# Seeeduino_v4_0.net
KiCad netlist of a schematic drawn in EAGLE
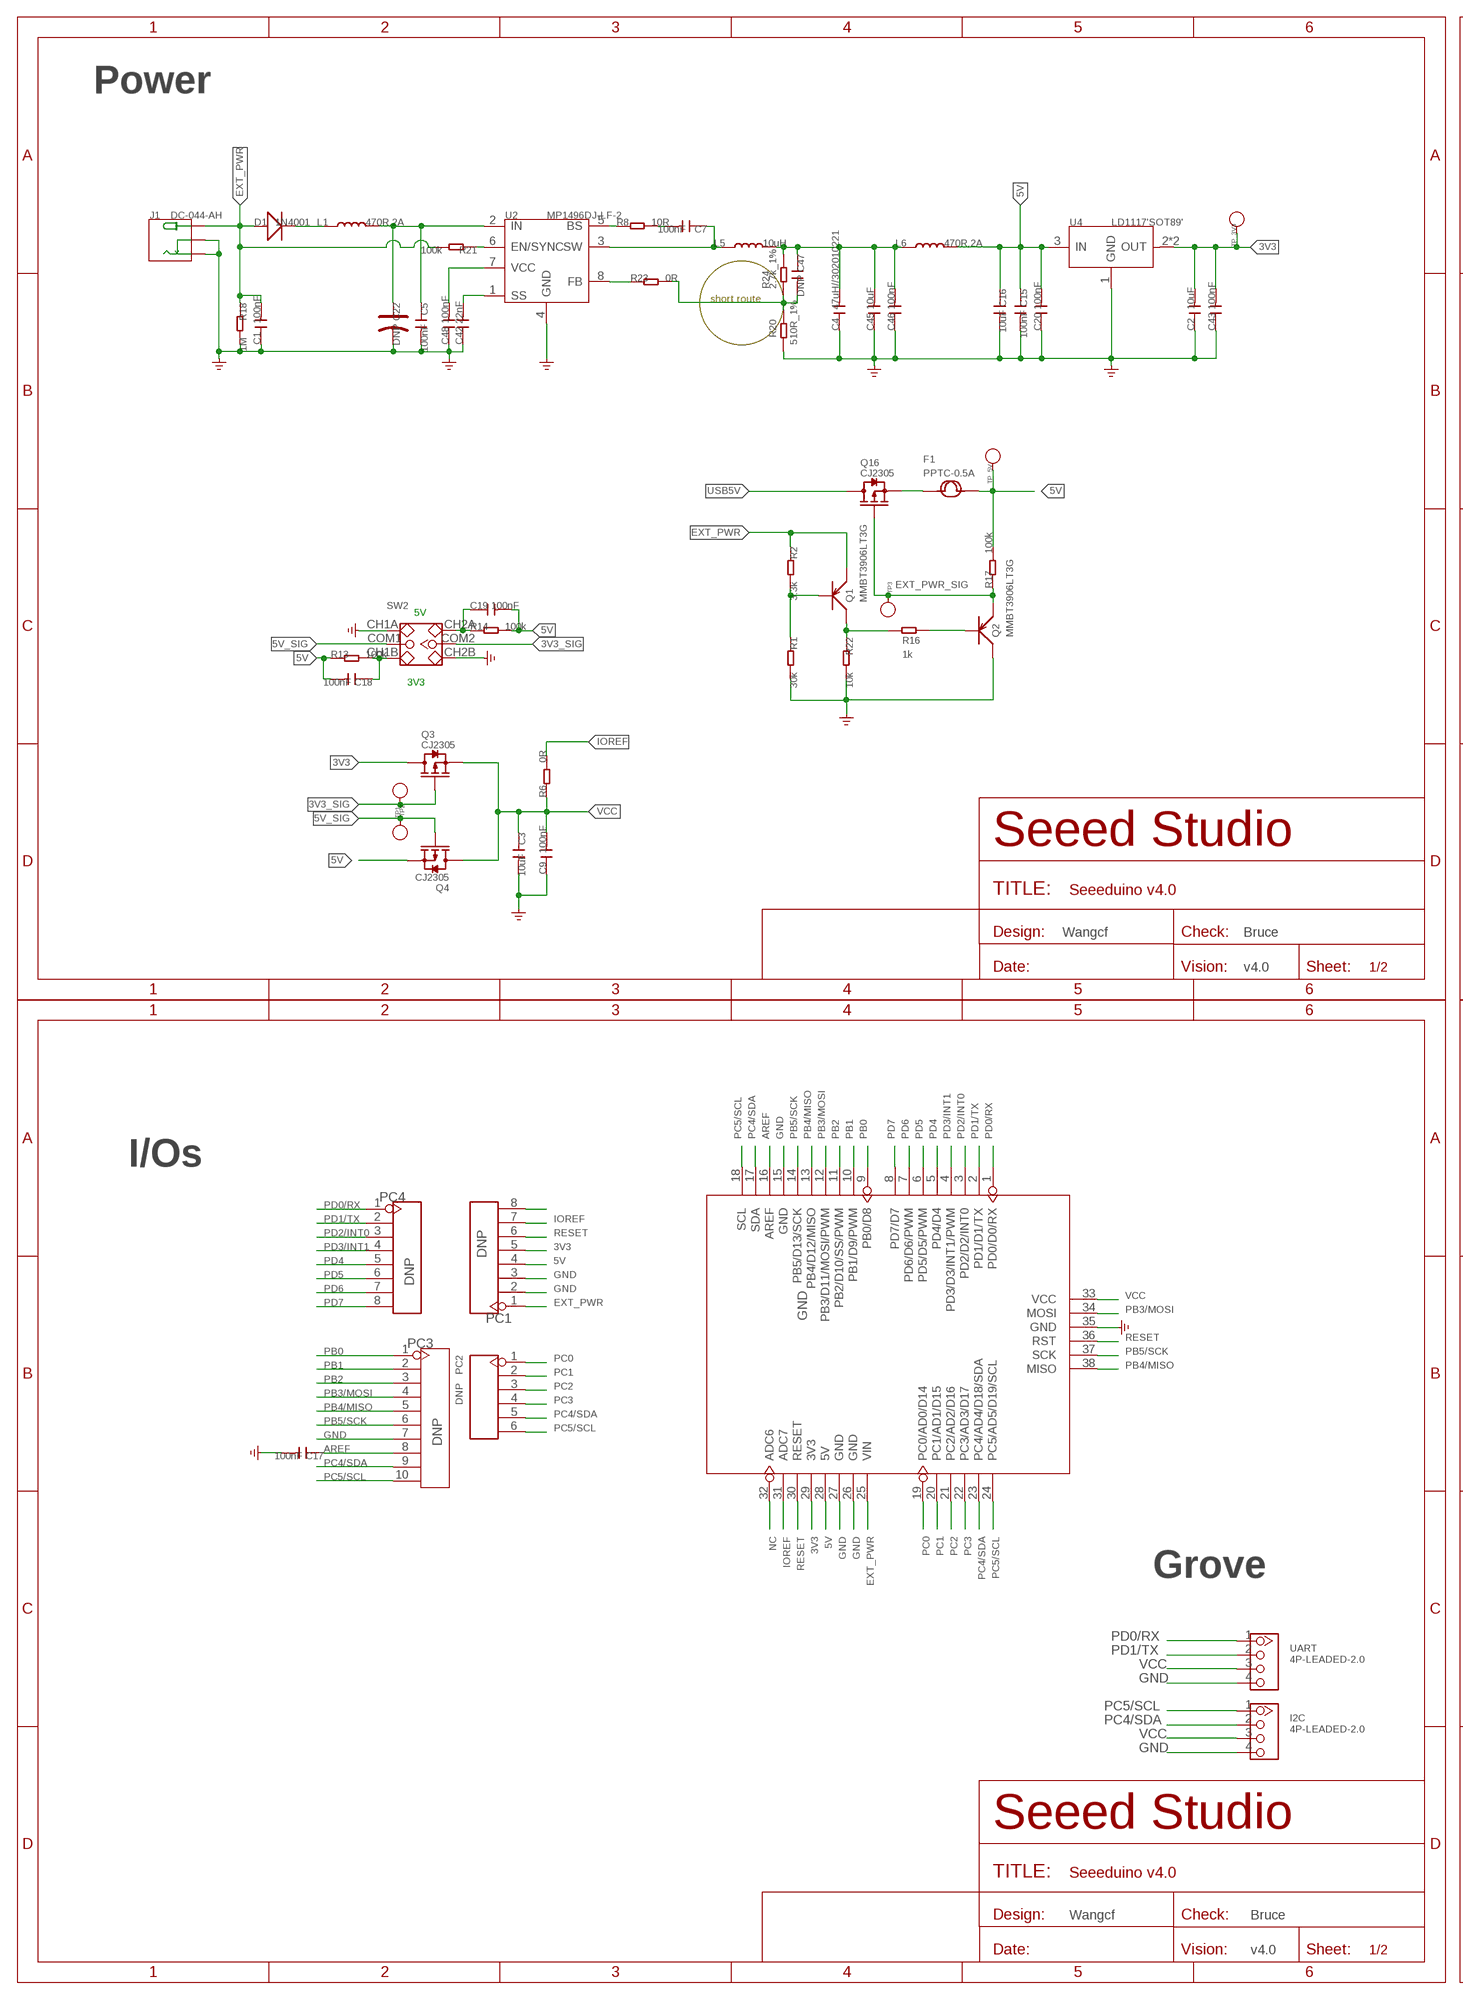
[diagram p0: schematic, sheet 1, part 1 of 2]
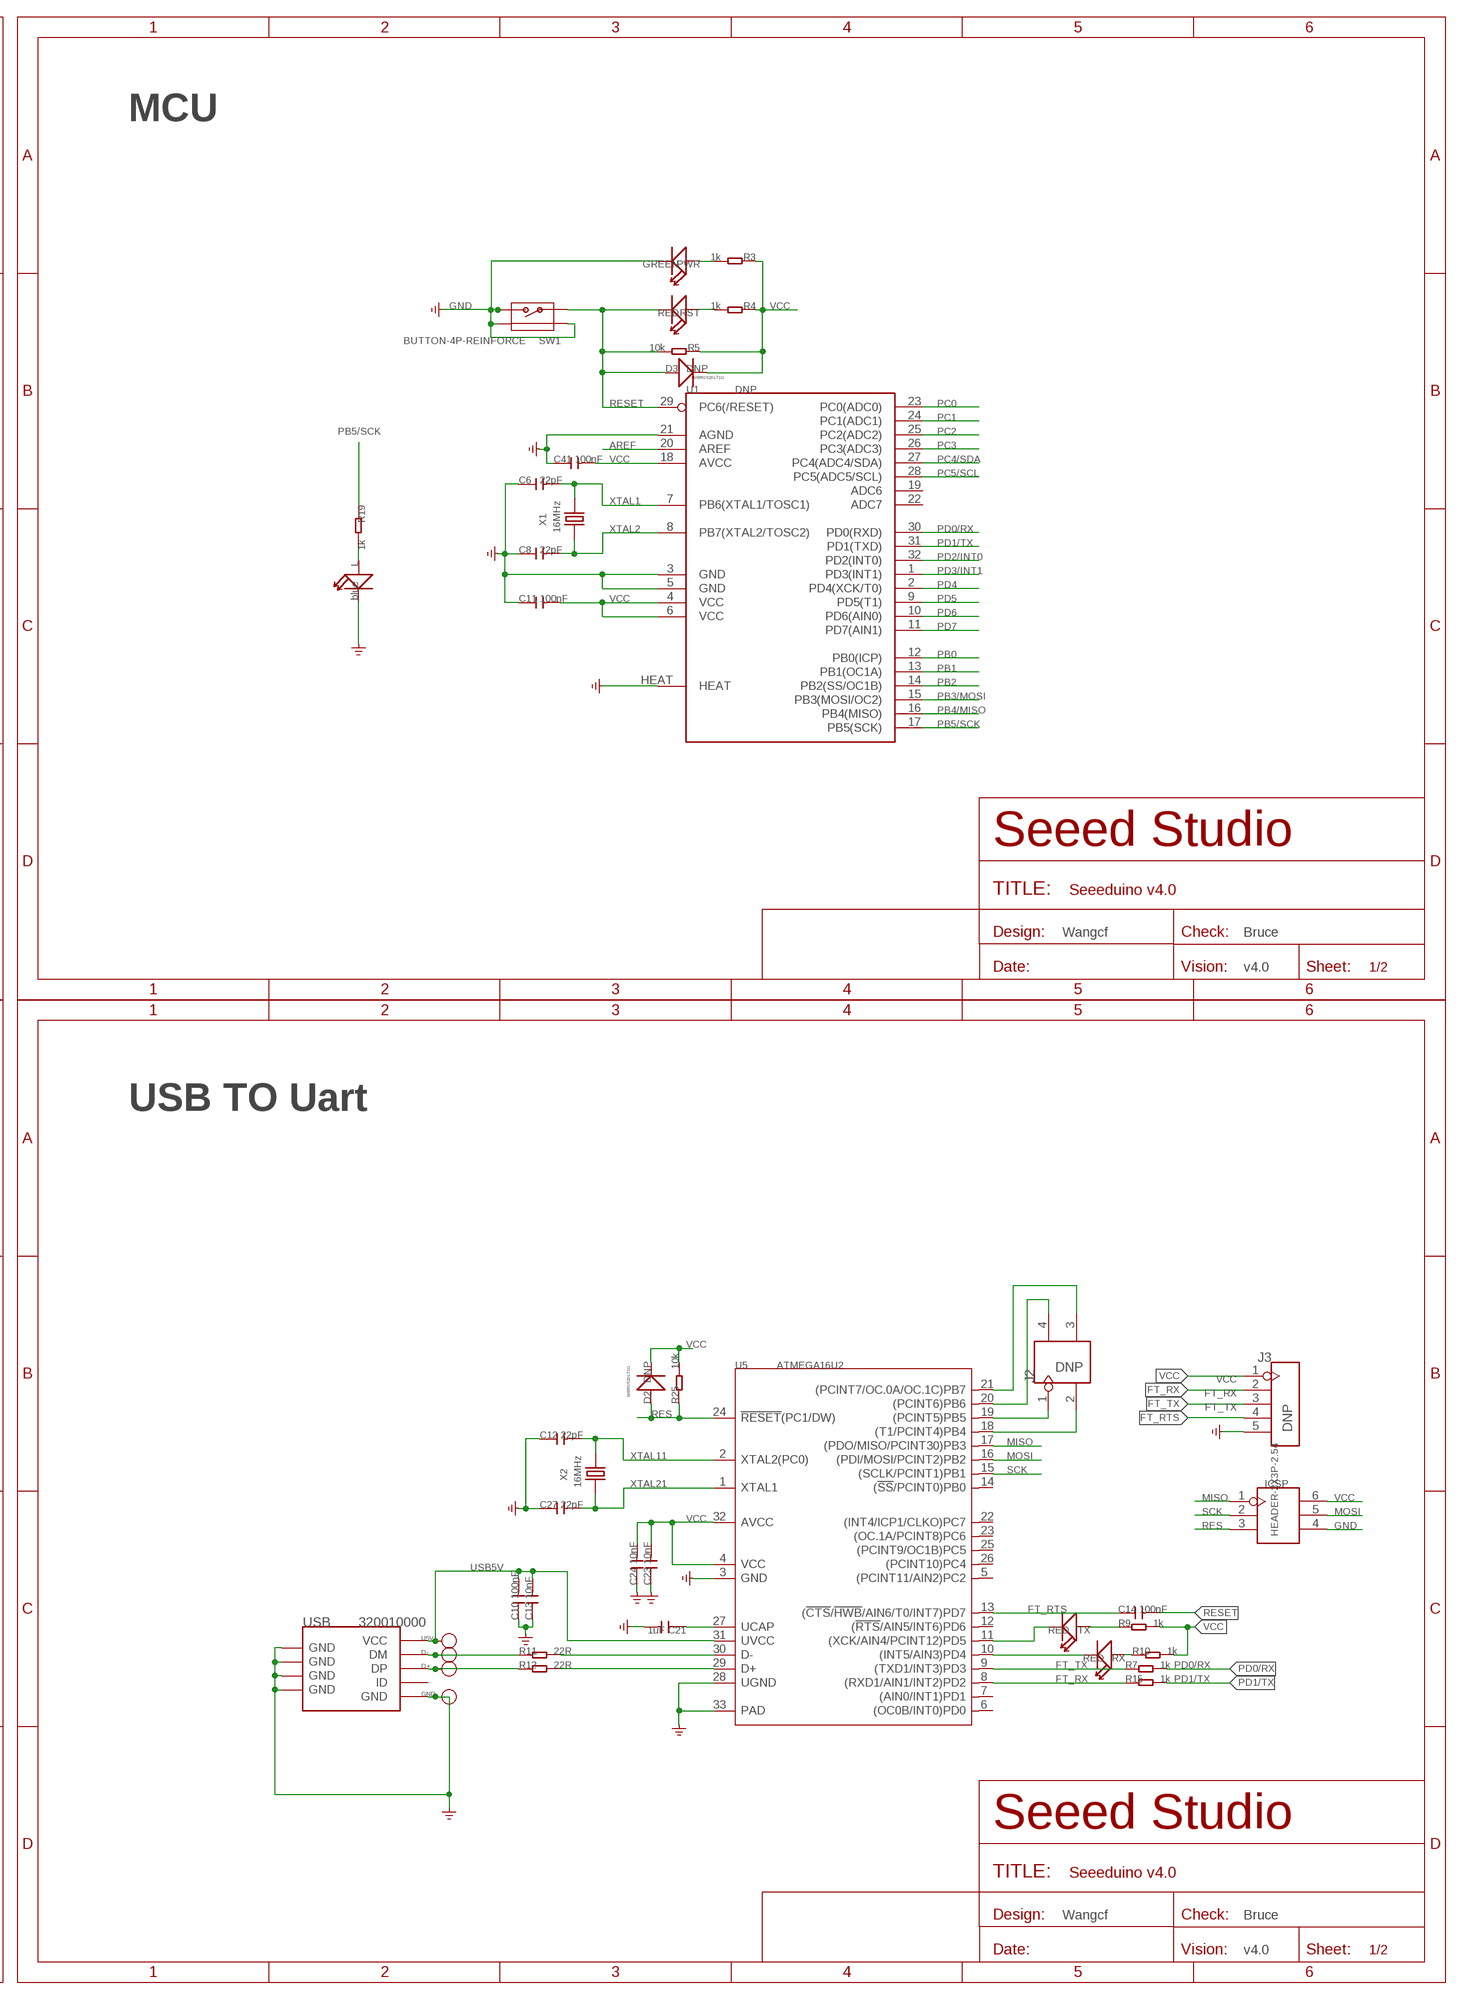
[diagram p1: schematic, sheet 1, part 2 of 2]
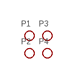
[diagram p2: schematic, sheet 2]

(export (version "E")
  (design (tool "Eeschema 10.0.6"))
  (components
    (comp (ref "C1")
      (value "100nF")
      (footprint "eagle-import:C0603")
      (libsource (lib "eagle-import") (part "C-0603"))
    )
    (comp (ref "C2")
      (value "10uF")
      (footprint "eagle-import:C0805")
      (libsource (lib "eagle-import") (part "C-0805"))
    )
    (comp (ref "C3")
      (value "10uF")
      (footprint "eagle-import:C0805")
      (libsource (lib "eagle-import") (part "C-0805"))
    )
    (comp (ref "C4")
      (value "47uH//302010221")
      (footprint "eagle-import:C1206")
      (libsource (lib "eagle-import") (part "C-1206"))
    )
    (comp (ref "C5")
      (value "100nF")
      (footprint "eagle-import:C0603")
      (libsource (lib "eagle-import") (part "C-0603"))
    )
    (comp (ref "C6")
      (value "22pF")
      (footprint "eagle-import:C0603")
      (libsource (lib "eagle-import") (part "C-0603"))
    )
    (comp (ref "C7")
      (value "100nF")
      (footprint "eagle-import:C0603")
      (libsource (lib "eagle-import") (part "C-0603"))
    )
    (comp (ref "C8")
      (value "22pF")
      (footprint "eagle-import:C0603")
      (libsource (lib "eagle-import") (part "C-0603"))
    )
    (comp (ref "C9")
      (value "100nF")
      (footprint "eagle-import:C0603")
      (libsource (lib "eagle-import") (part "C-0603"))
    )
    (comp (ref "C10")
      (value "100nF")
      (footprint "eagle-import:C0603")
      (libsource (lib "eagle-import") (part "C-0603"))
    )
    (comp (ref "C11")
      (value "100nF")
      (footprint "eagle-import:C0603")
      (libsource (lib "eagle-import") (part "C-0603"))
    )
    (comp (ref "C12")
      (value "22pF")
      (footprint "eagle-import:C0603")
      (libsource (lib "eagle-import") (part "C-0603"))
    )
    (comp (ref "C13")
      (value "10nF")
      (footprint "eagle-import:C0603")
      (libsource (lib "eagle-import") (part "C-0603"))
    )
    (comp (ref "C14")
      (value "100nF")
      (footprint "eagle-import:C0603")
      (libsource (lib "eagle-import") (part "C-0603"))
    )
    (comp (ref "C15")
      (value "100nF")
      (footprint "eagle-import:C0603")
      (libsource (lib "eagle-import") (part "C-0603"))
    )
    (comp (ref "C16")
      (value "10uF")
      (footprint "eagle-import:C0805")
      (libsource (lib "eagle-import") (part "C-0805"))
    )
    (comp (ref "C17")
      (value "100nF")
      (footprint "eagle-import:C0603")
      (libsource (lib "eagle-import") (part "C-0603"))
    )
    (comp (ref "C18")
      (value "100nF")
      (footprint "eagle-import:C0603")
      (libsource (lib "eagle-import") (part "C-0603"))
    )
    (comp (ref "C19")
      (value "100nF")
      (footprint "eagle-import:C0603")
      (libsource (lib "eagle-import") (part "C-0603"))
    )
    (comp (ref "C20")
      (value "100nF")
      (footprint "eagle-import:C0603")
      (libsource (lib "eagle-import") (part "C-0603"))
    )
    (comp (ref "C21")
      (value "1uF")
      (footprint "eagle-import:C0603")
      (libsource (lib "eagle-import") (part "C-0603"))
    )
    (comp (ref "C22")
      (value "DNP")
      (footprint "eagle-import:AVX-B")
      (libsource (lib "eagle-import") (part "CAP-AVX-B"))
    )
    (comp (ref "C23")
      (value "10nF")
      (footprint "eagle-import:C0603")
      (libsource (lib "eagle-import") (part "C-0603"))
    )
    (comp (ref "C24")
      (value "10nF")
      (footprint "eagle-import:C0603")
      (libsource (lib "eagle-import") (part "C-0603"))
    )
    (comp (ref "C27")
      (value "22pF")
      (footprint "eagle-import:C0603")
      (libsource (lib "eagle-import") (part "C-0603"))
    )
    (comp (ref "C41")
      (value "100nF")
      (footprint "eagle-import:C0603")
      (libsource (lib "eagle-import") (part "C-0603"))
    )
    (comp (ref "C42")
      (value "22nF")
      (footprint "eagle-import:C0603")
      (libsource (lib "eagle-import") (part "C-0603"))
    )
    (comp (ref "C43")
      (value "100nF")
      (footprint "eagle-import:C0603")
      (libsource (lib "eagle-import") (part "C-0603"))
    )
    (comp (ref "C45")
      (value "10uF")
      (footprint "eagle-import:C0805")
      (libsource (lib "eagle-import") (part "C-0805"))
    )
    (comp (ref "C46")
      (value "100nF")
      (footprint "eagle-import:C0603")
      (libsource (lib "eagle-import") (part "C-0603"))
    )
    (comp (ref "C47")
      (value "DNP")
      (footprint "eagle-import:C0603")
      (libsource (lib "eagle-import") (part "C-0603"))
    )
    (comp (ref "C48")
      (value "100nF")
      (footprint "eagle-import:C0603")
      (libsource (lib "eagle-import") (part "C-0603"))
    )
    (comp (ref "D+")
      (value "PAD-TEST-POINT'4545'")
      (footprint "eagle-import:TP_4545")
      (fields (field (name "PARTNO") "DNP"))
      (libsource (lib "eagle-import") (part "PAD-TEST-POINT'4545'"))
    )
    (comp (ref "D-")
      (value "PAD-TEST-POINT'4545'")
      (footprint "eagle-import:TP_4545")
      (fields (field (name "PARTNO") "DNP"))
      (libsource (lib "eagle-import") (part "PAD-TEST-POINT'4545'"))
    )
    (comp (ref "D1")
      (value "1N4001")
      (footprint "eagle-import:D2010")
      (libsource (lib "eagle-import") (part "D'DO-214AC'"))
    )
    (comp (ref "D2")
      (value "DNP")
      (footprint "eagle-import:SOD123")
      (libsource (lib "eagle-import") (part "D'1206'"))
    )
    (comp (ref "D3")
      (value "DNP")
      (footprint "eagle-import:SOD123")
      (libsource (lib "eagle-import") (part "D'1206'"))
    )
    (comp (ref "F1")
      (value "PPTC-0.5A")
      (footprint "eagle-import:F1206")
      (libsource (lib "eagle-import") (part "FUSE'1206'"))
    )
    (comp (ref "GND")
      (value "PAD-TEST-POINT'4545'")
      (footprint "eagle-import:TP_4545")
      (fields (field (name "PARTNO") "DNP"))
      (libsource (lib "eagle-import") (part "PAD-TEST-POINT'4545'"))
    )
    (comp (ref "I2C")
      (value "4P-LEADED-2.0")
      (footprint "eagle-import:4P-LEADED-2.0")
      (libsource (lib "eagle-import") (part "TWIG-2.0-LEADED"))
    )
    (comp (ref "ICSP")
      (value "HEADER-2X3P-2.54")
      (footprint "eagle-import:2X3P-2.0")
      (libsource (lib "eagle-import") (part "HEADER-2X3P-2.0"))
    )
    (comp (ref "J1")
      (value "DC-044-AH")
      (footprint "eagle-import:DC-404")
      (libsource (lib "eagle-import") (part "DC-044"))
    )
    (comp (ref "J2")
      (value "DNP")
      (footprint "eagle-import:2X2P-2.54")
      (libsource (lib "eagle-import") (part "HEADER-2X2P-2.54"))
    )
    (comp (ref "J3")
      (value "DNP")
      (footprint "eagle-import:5P-2.54")
      (libsource (lib "eagle-import") (part "HEADER-5P-2.54"))
    )
    (comp (ref "L")
      (value "blue")
      (footprint "eagle-import:LED-0603")
      (libsource (lib "eagle-import") (part "LED'0603'"))
    )
    (comp (ref "L1")
      (value "470R,2A")
      (footprint "eagle-import:L0805")
      (libsource (lib "eagle-import") (part "L'0805'"))
    )
    (comp (ref "L5")
      (value "10uH")
      (footprint "eagle-import:1813")
      (libsource (lib "eagle-import") (part "L'1813'"))
    )
    (comp (ref "L6")
      (value "470R,2A")
      (footprint "eagle-import:L0805")
      (libsource (lib "eagle-import") (part "L'0805'"))
    )
    (comp (ref "PC1")
      (value "DNP")
      (footprint "eagle-import:8P-2.54")
      (libsource (lib "eagle-import") (part "HEADER-8P-2.54"))
    )
    (comp (ref "PC2")
      (value "DNP")
      (footprint "eagle-import:6P-2.54-65_35MIL")
      (libsource (lib "eagle-import") (part "HEADER-6P-65/35MIL"))
    )
    (comp (ref "PC3")
      (value "DNP")
      (footprint "eagle-import:10P-2.54")
      (libsource (lib "eagle-import") (part "HEADER-10P-2.54"))
    )
    (comp (ref "PC4")
      (value "DNP")
      (footprint "eagle-import:8P-2.54")
      (libsource (lib "eagle-import") (part "HEADER-8P-2.54"))
    )
    (comp (ref "PWR")
      (value "GREEN")
      (footprint "eagle-import:LED-0603")
      (libsource (lib "eagle-import") (part "LED'0603'"))
    )
    (comp (ref "Q1")
      (value "MMBT3906LT3G")
      (footprint "eagle-import:SOT23")
      (libsource (lib "eagle-import") (part "TRANSISTOR-PNP-SOT23"))
    )
    (comp (ref "Q2")
      (value "MMBT3906LT3G")
      (footprint "eagle-import:SOT23")
      (libsource (lib "eagle-import") (part "TRANSISTOR-PNP-SOT23"))
    )
    (comp (ref "Q3")
      (value "CJ2305")
      (footprint "eagle-import:SOT23")
      (libsource (lib "eagle-import") (part "MOSFET-P'SI2323CDS/SI2305DS{lt}BR{gt}'"))
    )
    (comp (ref "Q4")
      (value "CJ2305")
      (footprint "eagle-import:SOT23")
      (libsource (lib "eagle-import") (part "MOSFET-P'SI2323CDS/SI2305DS{lt}BR{gt}'"))
    )
    (comp (ref "Q16")
      (value "CJ2305")
      (footprint "eagle-import:SOT23")
      (libsource (lib "eagle-import") (part "MOSFET-P'SI2323CDS/SI2305DS{lt}BR{gt}'"))
    )
    (comp (ref "R1")
      (value "30k")
      (footprint "eagle-import:R0603")
      (libsource (lib "eagle-import") (part "R-0603"))
    )
    (comp (ref "R2")
      (value "3.3k")
      (footprint "eagle-import:R0603")
      (libsource (lib "eagle-import") (part "R-0603"))
    )
    (comp (ref "R3")
      (value "1k")
      (footprint "eagle-import:R0603")
      (libsource (lib "eagle-import") (part "R-0603"))
    )
    (comp (ref "R4")
      (value "1k")
      (footprint "eagle-import:R0603")
      (libsource (lib "eagle-import") (part "R-0603"))
    )
    (comp (ref "R5")
      (value "10k")
      (footprint "eagle-import:R0603")
      (libsource (lib "eagle-import") (part "R-0603"))
    )
    (comp (ref "R6")
      (value "0R")
      (footprint "eagle-import:R0603")
      (libsource (lib "eagle-import") (part "R-0603"))
    )
    (comp (ref "R7")
      (value "1k")
      (footprint "eagle-import:R0603")
      (libsource (lib "eagle-import") (part "R-0603"))
    )
    (comp (ref "R8")
      (value "10R")
      (footprint "eagle-import:R0603")
      (libsource (lib "eagle-import") (part "R-0603"))
    )
    (comp (ref "R9")
      (value "1k")
      (footprint "eagle-import:R0603")
      (libsource (lib "eagle-import") (part "R-0603"))
    )
    (comp (ref "R10")
      (value "1k")
      (footprint "eagle-import:R0603")
      (libsource (lib "eagle-import") (part "R-0603"))
    )
    (comp (ref "R11")
      (value "22R")
      (footprint "eagle-import:R0603")
      (libsource (lib "eagle-import") (part "R-0603"))
    )
    (comp (ref "R12")
      (value "22R")
      (footprint "eagle-import:R0603")
      (libsource (lib "eagle-import") (part "R-0603"))
    )
    (comp (ref "R13")
      (value "100k")
      (footprint "eagle-import:R0603")
      (libsource (lib "eagle-import") (part "R-0603"))
    )
    (comp (ref "R14")
      (value "100k")
      (footprint "eagle-import:R0603")
      (libsource (lib "eagle-import") (part "R-0603"))
    )
    (comp (ref "R15")
      (value "1k")
      (footprint "eagle-import:R0603")
      (libsource (lib "eagle-import") (part "R-0603"))
    )
    (comp (ref "R16")
      (value "1k")
      (footprint "eagle-import:R0603")
      (libsource (lib "eagle-import") (part "R-0603"))
    )
    (comp (ref "R17")
      (value "100k")
      (footprint "eagle-import:R0603")
      (libsource (lib "eagle-import") (part "R-0603"))
    )
    (comp (ref "R18")
      (value "1M")
      (footprint "eagle-import:R0603")
      (libsource (lib "eagle-import") (part "R-0603"))
    )
    (comp (ref "R19")
      (value "1k")
      (footprint "eagle-import:R0603")
      (libsource (lib "eagle-import") (part "R-0603"))
    )
    (comp (ref "R20")
      (value "510R_1%")
      (footprint "eagle-import:R0603")
      (libsource (lib "eagle-import") (part "R-0603"))
    )
    (comp (ref "R21")
      (value "100k")
      (footprint "eagle-import:R0603")
      (libsource (lib "eagle-import") (part "R-0603"))
    )
    (comp (ref "R22")
      (value "10k")
      (footprint "eagle-import:R0603")
      (libsource (lib "eagle-import") (part "R-0603"))
    )
    (comp (ref "R23")
      (value "0R")
      (footprint "eagle-import:R0603")
      (libsource (lib "eagle-import") (part "R-0603"))
    )
    (comp (ref "R24")
      (value "2.7k_1%")
      (footprint "eagle-import:R0603")
      (libsource (lib "eagle-import") (part "R-0603"))
    )
    (comp (ref "R25")
      (value "10k")
      (footprint "eagle-import:R0603")
      (libsource (lib "eagle-import") (part "R-0603"))
    )
    (comp (ref "RST")
      (value "RED")
      (footprint "eagle-import:LED-0603")
      (libsource (lib "eagle-import") (part "LED'0603'"))
    )
    (comp (ref "RX")
      (value "RED")
      (footprint "eagle-import:LED-0603")
      (libsource (lib "eagle-import") (part "LED'0603'"))
    )
    (comp (ref "SW1")
      (value "BUTTON-4P-REINFORCE")
      (footprint "eagle-import:4P-SMD-7X3.5X3.5H")
      (libsource (lib "eagle-import") (part "BUTTON-4P-REINFORCE'TS-1188E'"))
    )
    (comp (ref "SW2")
      (value "SWITCH-2CH-6P-2.54")
      (footprint "eagle-import:6P-SMD-2CH-2.54-3.5X7.2")
      (libsource (lib "eagle-import") (part "SWITCH-2CH-6P-SMD"))
    )
    (comp (ref "TP1")
      (value "PAD-TEST-POINT'4545'")
      (footprint "eagle-import:TP_4545")
      (fields (field (name "PARTNO") "DNP"))
      (libsource (lib "eagle-import") (part "PAD-TEST-POINT'4545'"))
    )
    (comp (ref "TP2")
      (value "PAD-TEST-POINT'4545'")
      (footprint "eagle-import:TP_4545")
      (fields (field (name "PARTNO") "DNP"))
      (libsource (lib "eagle-import") (part "PAD-TEST-POINT'4545'"))
    )
    (comp (ref "TP3")
      (value "PAD-TEST-POINT'4545'")
      (footprint "eagle-import:TP_4545")
      (fields (field (name "PARTNO") "DNP"))
      (libsource (lib "eagle-import") (part "PAD-TEST-POINT'4545'"))
    )
    (comp (ref "TP_3V3")
      (value "PAD-TEST-POINT'4545'")
      (footprint "eagle-import:TP_4545")
      (fields (field (name "PARTNO") "DNP"))
      (libsource (lib "eagle-import") (part "PAD-TEST-POINT'4545'"))
    )
    (comp (ref "TP_5V")
      (value "PAD-TEST-POINT'4545'")
      (footprint "eagle-import:TP_4545")
      (fields (field (name "PARTNO") "DNP"))
      (libsource (lib "eagle-import") (part "PAD-TEST-POINT'4545'"))
    )
    (comp (ref "TX")
      (value "RED")
      (footprint "eagle-import:LED-0603")
      (libsource (lib "eagle-import") (part "LED'0603'"))
    )
    (comp (ref "U1")
      (value "DNP")
      (footprint "eagle-import:MLF32X")
      (libsource (lib "eagle-import") (part "MEGA8"))
    )
    (comp (ref "U2")
      (value "MP1496DJ-LF-2")
      (footprint "eagle-import:TSOT23-8")
      (libsource (lib "eagle-import") (part "MP1496DJ"))
    )
    (comp (ref "U3")
      (value "ARDUINO-38P")
      (footprint "eagle-import:ARDUINO-38P")
      (libsource (lib "eagle-import") (part "ARDUINO-38P"))
    )
    (comp (ref "U4")
      (value "LD1117'SOT89'")
      (footprint "eagle-import:SOT89")
      (libsource (lib "eagle-import") (part "LD1117'SOT89'"))
    )
    (comp (ref "U5")
      (value "ATMEGA16U2")
      (footprint "eagle-import:QFN32")
      (libsource (lib "eagle-import") (part "ATMEGA16U2"))
    )
    (comp (ref "U5V")
      (value "PAD-TEST-POINT'4545'")
      (footprint "eagle-import:TP_4545")
      (fields (field (name "PARTNO") "DNP"))
      (libsource (lib "eagle-import") (part "PAD-TEST-POINT'4545'"))
    )
    (comp (ref "UART")
      (value "4P-LEADED-2.0")
      (footprint "eagle-import:4P-LEADED-2.0")
      (libsource (lib "eagle-import") (part "TWIG-2.0-LEADED"))
    )
    (comp (ref "USB")
      (value "320010000")
      (footprint "eagle-import:MICRO-USB")
      (libsource (lib "eagle-import") (part "USB-MINIUSB-5P-MICRO"))
    )
    (comp (ref "X1")
      (value "16MHz")
      (footprint "eagle-import:2P-SMD-5X3.2")
      (libsource (lib "eagle-import") (part "CRYSTAL'5032'"))
    )
    (comp (ref "X2")
      (value "16MHz")
      (footprint "eagle-import:2P-SMD-5X3.2")
      (libsource (lib "eagle-import") (part "CRYSTAL'5032'"))
    )
    (comp (ref "P1")
      (value "PAD-MARK")
      (footprint "eagle-import:ROUND-MARK-1.0")
      (fields (field (name "PARTNO") "DNP"))
      (libsource (lib "eagle-import") (part "PAD-MARK"))
    )
    (comp (ref "P2")
      (value "PAD-MARK")
      (footprint "eagle-import:ROUND-MARK-1.0")
      (fields (field (name "PARTNO") "DNP"))
      (libsource (lib "eagle-import") (part "PAD-MARK"))
    )
    (comp (ref "P3")
      (value "PAD-MARK")
      (footprint "eagle-import:ROUND-MARK-1.0")
      (fields (field (name "PARTNO") "DNP"))
      (libsource (lib "eagle-import") (part "PAD-MARK"))
    )
    (comp (ref "P4")
      (value "PAD-MARK")
      (footprint "eagle-import:ROUND-MARK-1.0")
      (fields (field (name "PARTNO") "DNP"))
      (libsource (lib "eagle-import") (part "PAD-MARK"))
    )
  )
  (nets
    (net (code "1") (name "3V3") (class "Default")
      (node (ref "C2") (pin "2") (pinfunction "2_2") (pintype "passive"))
      (node (ref "C43") (pin "2") (pinfunction "2_2") (pintype "passive"))
      (node (ref "PC1") (pin "5") (pinfunction "5_5") (pintype "bidirectional"))
      (node (ref "Q3") (pin "3") (pinfunction "D_3") (pintype "passive"))
      (node (ref "TP_3V3") (pin "T") (pinfunction "T_T") (pintype "bidirectional"))
      (node (ref "U3") (pin "29") (pinfunction "3V3_29") (pintype "bidirectional"))
      (node (ref "U4") (pin "2") (pinfunction "OUT_2") (pintype "bidirectional"))
      (node (ref "U4") (pin "4") (pinfunction "OUT_4") (pintype "bidirectional"))
    )
    (net (code "2") (name "3V3_SIG") (class "Default")
      (node (ref "Q3") (pin "1") (pinfunction "G_1") (pintype "passive"))
      (node (ref "SW2") (pin "COM2") (pinfunction "COM2_COM2") (pintype "bidirectional"))
      (node (ref "TP1") (pin "T") (pinfunction "T_T") (pintype "bidirectional"))
    )
    (net (code "3") (name "5V") (class "Default")
      (node (ref "C15") (pin "1") (pinfunction "1_1") (pintype "passive"))
      (node (ref "C16") (pin "1") (pinfunction "1_1") (pintype "passive"))
      (node (ref "C18") (pin "2") (pinfunction "2_2") (pintype "passive"))
      (node (ref "C19") (pin "2") (pinfunction "2_2") (pintype "passive"))
      (node (ref "C20") (pin "2") (pinfunction "2_2") (pintype "passive"))
      (node (ref "F1") (pin "2") (pinfunction "2_2") (pintype "bidirectional"))
      (node (ref "L6") (pin "2") (pinfunction "2_2") (pintype "passive"))
      (node (ref "PC1") (pin "4") (pinfunction "4_4") (pintype "bidirectional"))
      (node (ref "Q4") (pin "2") (pinfunction "S_2") (pintype "passive"))
      (node (ref "R13") (pin "1") (pinfunction "1_1") (pintype "passive"))
      (node (ref "R14") (pin "2") (pinfunction "2_2") (pintype "passive"))
      (node (ref "R17") (pin "2") (pinfunction "2_2") (pintype "passive"))
      (node (ref "TP_5V") (pin "T") (pinfunction "T_T") (pintype "bidirectional"))
      (node (ref "U3") (pin "28") (pinfunction "5V_28") (pintype "bidirectional"))
      (node (ref "U4") (pin "3") (pinfunction "IN_3") (pintype "bidirectional"))
    )
    (net (code "4") (name "5V_SIG") (class "Default")
      (node (ref "Q4") (pin "1") (pinfunction "G_1") (pintype "passive"))
      (node (ref "SW2") (pin "COM1") (pinfunction "COM1_COM1") (pintype "bidirectional"))
      (node (ref "TP2") (pin "T") (pinfunction "T_T") (pintype "bidirectional"))
    )
    (net (code "5") (name "AREF") (class "Default")
      (node (ref "C17") (pin "1") (pinfunction "1_1") (pintype "passive"))
      (node (ref "PC3") (pin "8") (pinfunction "8_8") (pintype "bidirectional"))
      (node (ref "U1") (pin "20") (pinfunction "AREF_20") (pintype "bidirectional"))
      (node (ref "U3") (pin "16") (pinfunction "AREF_16") (pintype "bidirectional"))
    )
    (net (code "6") (name "EXT_PWR") (class "Default")
      (node (ref "C1") (pin "2") (pinfunction "2_2") (pintype "passive"))
      (node (ref "D1") (pin "+") (pinfunction "+_+") (pintype "passive"))
      (node (ref "J1") (pin "+") (pinfunction "+_+") (pintype "bidirectional"))
      (node (ref "PC1") (pin "1") (pinfunction "1_1") (pintype "bidirectional"))
      (node (ref "Q1") (pin "2") (pinfunction "E_2") (pintype "passive"))
      (node (ref "R18") (pin "1") (pinfunction "1_1") (pintype "passive"))
      (node (ref "R2") (pin "1") (pinfunction "1_1") (pintype "passive"))
      (node (ref "R21") (pin "2") (pinfunction "2_2") (pintype "passive"))
      (node (ref "U3") (pin "25") (pinfunction "VIN_25") (pintype "bidirectional"))
    )
    (net (code "7") (name "EXT_PWR_SIG") (class "Default")
      (node (ref "Q16") (pin "1") (pinfunction "G_1") (pintype "passive"))
      (node (ref "Q2") (pin "2") (pinfunction "E_2") (pintype "passive"))
      (node (ref "R17") (pin "1") (pinfunction "1_1") (pintype "passive"))
      (node (ref "TP3") (pin "T") (pinfunction "T_T") (pintype "bidirectional"))
    )
    (net (code "8") (name "FT_RTS") (class "Default")
      (node (ref "C14") (pin "1") (pinfunction "1_1") (pintype "passive"))
      (node (ref "J3") (pin "4") (pinfunction "4_4") (pintype "bidirectional"))
      (node (ref "U5") (pin "13") (pinfunction "(~{CTS}/~{HWB}/AIN6/T0/INT7)PD7_13") (pintype "bidirectional"))
    )
    (net (code "9") (name "FT_RX") (class "Default")
      (node (ref "J3") (pin "2") (pinfunction "2_2") (pintype "bidirectional"))
      (node (ref "R15") (pin "1") (pinfunction "1_1") (pintype "passive"))
      (node (ref "U5") (pin "8") (pinfunction "(RXD1/AIN1/INT2)PD2_8") (pintype "bidirectional"))
    )
    (net (code "10") (name "FT_TX") (class "Default")
      (node (ref "J3") (pin "3") (pinfunction "3_3") (pintype "bidirectional"))
      (node (ref "R7") (pin "1") (pinfunction "1_1") (pintype "passive"))
      (node (ref "U5") (pin "9") (pinfunction "(TXD1/INT3)PD3_9") (pintype "bidirectional"))
    )
    (net (code "11") (name "GND") (class "Default")
      (node (ref "C1") (pin "1") (pinfunction "1_1") (pintype "passive"))
      (node (ref "C10") (pin "1") (pinfunction "1_1") (pintype "passive"))
      (node (ref "C11") (pin "1") (pinfunction "1_1") (pintype "passive"))
      (node (ref "C12") (pin "1") (pinfunction "1_1") (pintype "passive"))
      (node (ref "C13") (pin "1") (pinfunction "1_1") (pintype "passive"))
      (node (ref "C15") (pin "2") (pinfunction "2_2") (pintype "passive"))
      (node (ref "C16") (pin "2") (pinfunction "2_2") (pintype "passive"))
      (node (ref "C17") (pin "2") (pinfunction "2_2") (pintype "passive"))
      (node (ref "C2") (pin "1") (pinfunction "1_1") (pintype "passive"))
      (node (ref "C20") (pin "1") (pinfunction "1_1") (pintype "passive"))
      (node (ref "C21") (pin "2") (pinfunction "2_2") (pintype "passive"))
      (node (ref "C22") (pin "-") (pinfunction "-_-") (pintype "passive"))
      (node (ref "C23") (pin "1") (pinfunction "1_1") (pintype "passive"))
      (node (ref "C24") (pin "1") (pinfunction "1_1") (pintype "passive"))
      (node (ref "C27") (pin "1") (pinfunction "1_1") (pintype "passive"))
      (node (ref "C3") (pin "2") (pinfunction "2_2") (pintype "passive"))
      (node (ref "C4") (pin "1") (pinfunction "1_1") (pintype "passive"))
      (node (ref "C41") (pin "1") (pinfunction "1_1") (pintype "passive"))
      (node (ref "C42") (pin "1") (pinfunction "1_1") (pintype "passive"))
      (node (ref "C43") (pin "1") (pinfunction "1_1") (pintype "passive"))
      (node (ref "C45") (pin "1") (pinfunction "1_1") (pintype "passive"))
      (node (ref "C46") (pin "1") (pinfunction "1_1") (pintype "passive"))
      (node (ref "C48") (pin "1") (pinfunction "1_1") (pintype "passive"))
      (node (ref "C5") (pin "2") (pinfunction "2_2") (pintype "passive"))
      (node (ref "C6") (pin "1") (pinfunction "1_1") (pintype "passive"))
      (node (ref "C8") (pin "1") (pinfunction "1_1") (pintype "passive"))
      (node (ref "C9") (pin "1") (pinfunction "1_1") (pintype "passive"))
      (node (ref "GND") (pin "T") (pinfunction "T_T") (pintype "bidirectional"))
      (node (ref "I2C") (pin "4") (pinfunction "4_4") (pintype "bidirectional"))
      (node (ref "ICSP") (pin "4") (pinfunction "4_4") (pintype "bidirectional"))
      (node (ref "J1") (pin "-") (pinfunction "-_-") (pintype "bidirectional"))
      (node (ref "J1") (pin "CDN") (pinfunction "CDN_CDN") (pintype "bidirectional"))
      (node (ref "J3") (pin "5") (pinfunction "5_5") (pintype "bidirectional"))
      (node (ref "L") (pin "-") (pinfunction "-_-") (pintype "passive"))
      (node (ref "PC1") (pin "2") (pinfunction "2_2") (pintype "bidirectional"))
      (node (ref "PC1") (pin "3") (pinfunction "3_3") (pintype "bidirectional"))
      (node (ref "PC3") (pin "7") (pinfunction "7_7") (pintype "bidirectional"))
      (node (ref "PWR") (pin "-") (pinfunction "-_-") (pintype "passive"))
      (node (ref "Q2") (pin "3") (pinfunction "C_3") (pintype "passive"))
      (node (ref "R1") (pin "2") (pinfunction "2_2") (pintype "passive"))
      (node (ref "R18") (pin "2") (pinfunction "2_2") (pintype "passive"))
      (node (ref "R20") (pin "1") (pinfunction "1_1") (pintype "passive"))
      (node (ref "R22") (pin "2") (pinfunction "2_2") (pintype "passive"))
      (node (ref "SW1") (pin "2") (pinfunction "2_2") (pintype "bidirectional"))
      (node (ref "SW1") (pin "S1") (pinfunction "S1_S1") (pintype "bidirectional"))
      (node (ref "SW1") (pin "S2") (pinfunction "S2_S2") (pintype "bidirectional"))
      (node (ref "SW2") (pin "CH1A") (pinfunction "CH1A_CH1A") (pintype "bidirectional"))
      (node (ref "SW2") (pin "CH2B") (pinfunction "CH2B_CH2B") (pintype "bidirectional"))
      (node (ref "U1") (pin "21") (pinfunction "AGND_21") (pintype "bidirectional"))
      (node (ref "U1") (pin "3") (pinfunction "GND_3") (pintype "bidirectional"))
      (node (ref "U1") (pin "5") (pinfunction "GND_5") (pintype "bidirectional"))
      (node (ref "U1") (pin "HEAT") (pinfunction "HEAT_HEAT") (pintype "bidirectional"))
      (node (ref "U2") (pin "4") (pinfunction "GND_4") (pintype "bidirectional"))
      (node (ref "U3") (pin "15") (pinfunction "GND_15") (pintype "bidirectional"))
      (node (ref "U3") (pin "26") (pinfunction "GND_26") (pintype "bidirectional"))
      (node (ref "U3") (pin "27") (pinfunction "GND_27") (pintype "bidirectional"))
      (node (ref "U3") (pin "35") (pinfunction "GND_35") (pintype "bidirectional"))
      (node (ref "U4") (pin "1") (pinfunction "GND_1") (pintype "bidirectional"))
      (node (ref "U5") (pin "28") (pinfunction "UGND_28") (pintype "bidirectional"))
      (node (ref "U5") (pin "3") (pinfunction "GND_3") (pintype "bidirectional"))
      (node (ref "U5") (pin "33") (pinfunction "PAD_33") (pintype "bidirectional"))
      (node (ref "UART") (pin "4") (pinfunction "4_4") (pintype "bidirectional"))
      (node (ref "USB") (pin "5") (pinfunction "GND_5") (pintype "bidirectional"))
      (node (ref "USB") (pin "S1") (pinfunction "GND_S1") (pintype "bidirectional"))
      (node (ref "USB") (pin "S2") (pinfunction "GND_S2") (pintype "bidirectional"))
      (node (ref "USB") (pin "S3") (pinfunction "GND_S3") (pintype "bidirectional"))
      (node (ref "USB") (pin "S4") (pinfunction "GND_S4") (pintype "bidirectional"))
      (node (ref "USB") (pin "S5") (pinfunction "GND_S5") (pintype "bidirectional"))
      (node (ref "USB") (pin "S6") (pinfunction "GND_S6") (pintype "bidirectional"))
    )
    (net (code "12") (name "IOREF") (class "Default")
      (node (ref "PC1") (pin "7") (pinfunction "7_7") (pintype "bidirectional"))
      (node (ref "R6") (pin "2") (pinfunction "2_2") (pintype "passive"))
      (node (ref "U3") (pin "31") (pinfunction "ADC7_31") (pintype "bidirectional"))
    )
    (net (code "13") (name "MISO") (class "Default")
      (node (ref "ICSP") (pin "1") (pinfunction "1_1") (pintype "bidirectional"))
      (node (ref "U5") (pin "17") (pinfunction "(PDO/MISO/PCINT30)PB3_17") (pintype "bidirectional"))
    )
    (net (code "14") (name "MOSI") (class "Default")
      (node (ref "ICSP") (pin "5") (pinfunction "5_5") (pintype "bidirectional"))
      (node (ref "U5") (pin "16") (pinfunction "(PDI/MOSI/PCINT2)PB2_16") (pintype "bidirectional"))
    )
    (net (code "15") (name "NC") (class "Default")
      (node (ref "PC1") (pin "8") (pinfunction "8_8") (pintype "bidirectional"))
      (node (ref "U3") (pin "32") (pinfunction "ADC6_32") (pintype "bidirectional"))
    )
    (net (code "16") (name "Net-(C4-Pad2)") (class "Default")
      (node (ref "C4") (pin "2") (pinfunction "2_2") (pintype "passive"))
      (node (ref "C45") (pin "2") (pinfunction "2_2") (pintype "passive"))
      (node (ref "C46") (pin "2") (pinfunction "2_2") (pintype "passive"))
      (node (ref "C47") (pin "1") (pinfunction "1_1") (pintype "passive"))
      (node (ref "L5") (pin "2") (pinfunction "2_2") (pintype "passive"))
      (node (ref "L6") (pin "1") (pinfunction "1_1") (pintype "passive"))
      (node (ref "R24") (pin "1") (pinfunction "1_1") (pintype "passive"))
    )
    (net (code "17") (name "Net-(C7-Pad2)") (class "Default")
      (node (ref "C7") (pin "2") (pinfunction "2_2") (pintype "passive"))
      (node (ref "R8") (pin "2") (pinfunction "2_2") (pintype "passive"))
    )
    (net (code "18") (name "Net-(C18-Pad1)") (class "Default")
      (node (ref "C18") (pin "1") (pinfunction "1_1") (pintype "passive"))
      (node (ref "R13") (pin "2") (pinfunction "2_2") (pintype "passive"))
      (node (ref "SW2") (pin "CH1B") (pinfunction "CH1B_CH1B") (pintype "bidirectional"))
    )
    (net (code "19") (name "Net-(C19-Pad1)") (class "Default")
      (node (ref "C19") (pin "1") (pinfunction "1_1") (pintype "passive"))
      (node (ref "R14") (pin "1") (pinfunction "1_1") (pintype "passive"))
      (node (ref "SW2") (pin "CH2A") (pinfunction "CH2A_CH2A") (pintype "bidirectional"))
    )
    (net (code "20") (name "Net-(C47-Pad2)") (class "Default")
      (node (ref "C47") (pin "2") (pinfunction "2_2") (pintype "passive"))
      (node (ref "R20") (pin "2") (pinfunction "2_2") (pintype "passive"))
      (node (ref "R23") (pin "2") (pinfunction "2_2") (pintype "passive"))
      (node (ref "R24") (pin "2") (pinfunction "2_2") (pintype "passive"))
    )
    (net (code "21") (name "Net-(D1-Pad-)") (class "Default")
      (node (ref "D1") (pin "-") (pinfunction "-_-") (pintype "passive"))
      (node (ref "L1") (pin "1") (pinfunction "1_1") (pintype "passive"))
    )
    (net (code "22") (name "Net-(L-Pad+)") (class "Default")
      (node (ref "L") (pin "+") (pinfunction "+_+") (pintype "passive"))
      (node (ref "R19") (pin "2") (pinfunction "2_2") (pintype "passive"))
    )
    (net (code "23") (name "Net-(PWR-Pad+)") (class "Default")
      (node (ref "PWR") (pin "+") (pinfunction "+_+") (pintype "passive"))
      (node (ref "R3") (pin "2") (pinfunction "2_2") (pintype "passive"))
    )
    (net (code "24") (name "Net-(Q1-B)") (class "Default")
      (node (ref "Q1") (pin "1") (pinfunction "B_1") (pintype "passive"))
      (node (ref "R1") (pin "1") (pinfunction "1_1") (pintype "passive"))
      (node (ref "R2") (pin "2") (pinfunction "2_2") (pintype "passive"))
    )
    (net (code "25") (name "Net-(Q1-C)") (class "Default")
      (node (ref "Q1") (pin "3") (pinfunction "C_3") (pintype "passive"))
      (node (ref "R16") (pin "1") (pinfunction "1_1") (pintype "passive"))
      (node (ref "R22") (pin "1") (pinfunction "1_1") (pintype "passive"))
    )
    (net (code "26") (name "Net-(Q2-B)") (class "Default")
      (node (ref "Q2") (pin "1") (pinfunction "B_1") (pintype "passive"))
      (node (ref "R16") (pin "2") (pinfunction "2_2") (pintype "passive"))
    )
    (net (code "27") (name "Net-(Q16-S)") (class "Default")
      (node (ref "F1") (pin "1") (pinfunction "1_1") (pintype "bidirectional"))
      (node (ref "Q16") (pin "2") (pinfunction "S_2") (pintype "passive"))
    )
    (net (code "28") (name "Net-(R4-Pad2)") (class "Default")
      (node (ref "R4") (pin "2") (pinfunction "2_2") (pintype "passive"))
      (node (ref "RST") (pin "+") (pinfunction "+_+") (pintype "passive"))
    )
    (net (code "29") (name "Net-(R9-Pad1)") (class "Default")
      (node (ref "R9") (pin "1") (pinfunction "1_1") (pintype "passive"))
      (node (ref "TX") (pin "+") (pinfunction "+_+") (pintype "passive"))
    )
    (net (code "30") (name "Net-(R10-Pad1)") (class "Default")
      (node (ref "R10") (pin "1") (pinfunction "1_1") (pintype "passive"))
      (node (ref "RX") (pin "+") (pinfunction "+_+") (pintype "passive"))
    )
    (net (code "31") (name "Net-(U2-BS)") (class "Default")
      (node (ref "R8") (pin "1") (pinfunction "1_1") (pintype "passive"))
      (node (ref "U2") (pin "5") (pinfunction "BS_5") (pintype "bidirectional"))
    )
    (net (code "32") (name "Net-(U2-EN{slash}SYNC)") (class "Default")
      (node (ref "R21") (pin "1") (pinfunction "1_1") (pintype "passive"))
      (node (ref "U2") (pin "6") (pinfunction "EN/SYNC_6") (pintype "bidirectional"))
    )
    (net (code "33") (name "Net-(U2-FB)") (class "Default")
      (node (ref "R23") (pin "1") (pinfunction "1_1") (pintype "passive"))
      (node (ref "U2") (pin "8") (pinfunction "FB_8") (pintype "bidirectional"))
    )
    (net (code "34") (name "Net-(U2-IN)") (class "Default")
      (node (ref "C22") (pin "+") (pinfunction "+_+") (pintype "passive"))
      (node (ref "C5") (pin "1") (pinfunction "1_1") (pintype "passive"))
      (node (ref "L1") (pin "2") (pinfunction "2_2") (pintype "passive"))
      (node (ref "U2") (pin "2") (pinfunction "IN_2") (pintype "bidirectional"))
    )
    (net (code "35") (name "Net-(U2-SS)") (class "Default")
      (node (ref "C42") (pin "2") (pinfunction "2_2") (pintype "passive"))
      (node (ref "U2") (pin "1") (pinfunction "SS_1") (pintype "bidirectional"))
    )
    (net (code "36") (name "Net-(U2-SW)") (class "Default")
      (node (ref "C7") (pin "1") (pinfunction "1_1") (pintype "passive"))
      (node (ref "L5") (pin "1") (pinfunction "1_1") (pintype "passive"))
      (node (ref "U2") (pin "3") (pinfunction "SW_3") (pintype "bidirectional"))
    )
    (net (code "37") (name "Net-(U2-VCC)") (class "Default")
      (node (ref "C48") (pin "2") (pinfunction "2_2") (pintype "passive"))
      (node (ref "U2") (pin "7") (pinfunction "VCC_7") (pintype "bidirectional"))
    )
    (net (code "38") (name "Net-(U5-(INT5{slash}AIN3)PD4)") (class "Default")
      (node (ref "RX") (pin "-") (pinfunction "-_-") (pintype "passive"))
      (node (ref "U5") (pin "10") (pinfunction "(INT5/AIN3)PD4_10") (pintype "bidirectional"))
    )
    (net (code "39") (name "Net-(U5-(PCINT5)PB5)") (class "Default")
      (node (ref "J2") (pin "1") (pinfunction "1_1") (pintype "bidirectional"))
      (node (ref "U5") (pin "19") (pinfunction "(PCINT5)PB5_19") (pintype "bidirectional"))
    )
    (net (code "40") (name "Net-(U5-(PCINT6)PB6)") (class "Default")
      (node (ref "J2") (pin "4") (pinfunction "4_4") (pintype "bidirectional"))
      (node (ref "U5") (pin "20") (pinfunction "(PCINT6)PB6_20") (pintype "bidirectional"))
    )
    (net (code "41") (name "Net-(U5-(PCINT7{slash}OC.0A{slash}OC.1C)PB7)") (class "Default")
      (node (ref "J2") (pin "3") (pinfunction "3_3") (pintype "bidirectional"))
      (node (ref "U5") (pin "21") (pinfunction "(PCINT7/OC.0A/OC.1C)PB7_21") (pintype "bidirectional"))
    )
    (net (code "42") (name "Net-(U5-(T1{slash}PCINT4)PB4)") (class "Default")
      (node (ref "J2") (pin "2") (pinfunction "2_2") (pintype "bidirectional"))
      (node (ref "U5") (pin "18") (pinfunction "(T1/PCINT4)PB4_18") (pintype "bidirectional"))
    )
    (net (code "43") (name "Net-(U5-(XCK{slash}AIN4{slash}PCINT12)PD5)") (class "Default")
      (node (ref "TX") (pin "-") (pinfunction "-_-") (pintype "passive"))
      (node (ref "U5") (pin "11") (pinfunction "(XCK/AIN4/PCINT12)PD5_11") (pintype "bidirectional"))
    )
    (net (code "44") (name "Net-(U5-D+)") (class "Default")
      (node (ref "R12") (pin "2") (pinfunction "2_2") (pintype "passive"))
      (node (ref "U5") (pin "29") (pinfunction "D+_29") (pintype "bidirectional"))
    )
    (net (code "45") (name "Net-(U5-D-)") (class "Default")
      (node (ref "R11") (pin "2") (pinfunction "2_2") (pintype "passive"))
      (node (ref "U5") (pin "30") (pinfunction "D-_30") (pintype "bidirectional"))
    )
    (net (code "46") (name "Net-(U5-UCAP)") (class "Default")
      (node (ref "C21") (pin "1") (pinfunction "1_1") (pintype "passive"))
      (node (ref "U5") (pin "27") (pinfunction "UCAP_27") (pintype "bidirectional"))
    )
    (net (code "47") (name "Net-(USB-DM)") (class "Default")
      (node (ref "D-") (pin "T") (pinfunction "T_T") (pintype "bidirectional"))
      (node (ref "R11") (pin "1") (pinfunction "1_1") (pintype "passive"))
      (node (ref "USB") (pin "2") (pinfunction "DM_2") (pintype "bidirectional"))
    )
    (net (code "48") (name "Net-(USB-DP)") (class "Default")
      (node (ref "D+") (pin "T") (pinfunction "T_T") (pintype "bidirectional"))
      (node (ref "R12") (pin "1") (pinfunction "1_1") (pintype "passive"))
      (node (ref "USB") (pin "3") (pinfunction "DP_3") (pintype "bidirectional"))
    )
    (net (code "49") (name "PB0") (class "Default")
      (node (ref "PC3") (pin "1") (pinfunction "1_1") (pintype "bidirectional"))
      (node (ref "U1") (pin "12") (pinfunction "PB0(ICP)_12") (pintype "bidirectional"))
      (node (ref "U3") (pin "9") (pinfunction "PB0/D8_9") (pintype "bidirectional"))
    )
    (net (code "50") (name "PB1") (class "Default")
      (node (ref "PC3") (pin "2") (pinfunction "2_2") (pintype "bidirectional"))
      (node (ref "U1") (pin "13") (pinfunction "PB1(OC1A)_13") (pintype "bidirectional"))
      (node (ref "U3") (pin "10") (pinfunction "PB1/D9/PWM_10") (pintype "bidirectional"))
    )
    (net (code "51") (name "PB2") (class "Default")
      (node (ref "PC3") (pin "3") (pinfunction "3_3") (pintype "bidirectional"))
      (node (ref "U1") (pin "14") (pinfunction "PB2(SS/OC1B)_14") (pintype "bidirectional"))
      (node (ref "U3") (pin "11") (pinfunction "PB2/D10/SS/PWM_11") (pintype "bidirectional"))
    )
    (net (code "52") (name "PB3{slash}MOSI") (class "Default")
      (node (ref "PC3") (pin "4") (pinfunction "4_4") (pintype "bidirectional"))
      (node (ref "U1") (pin "15") (pinfunction "PB3(MOSI/OC2)_15") (pintype "bidirectional"))
      (node (ref "U3") (pin "12") (pinfunction "PB3/D11/MOSI/PWM_12") (pintype "bidirectional"))
      (node (ref "U3") (pin "34") (pinfunction "MOSI_34") (pintype "bidirectional"))
    )
    (net (code "53") (name "PB4{slash}MISO") (class "Default")
      (node (ref "PC3") (pin "5") (pinfunction "5_5") (pintype "bidirectional"))
      (node (ref "U1") (pin "16") (pinfunction "PB4(MISO)_16") (pintype "bidirectional"))
      (node (ref "U3") (pin "13") (pinfunction "PB4/D12/MISO_13") (pintype "bidirectional"))
      (node (ref "U3") (pin "38") (pinfunction "MISO_38") (pintype "bidirectional"))
    )
    (net (code "54") (name "PB5{slash}SCK") (class "Default")
      (node (ref "PC3") (pin "6") (pinfunction "6_6") (pintype "bidirectional"))
      (node (ref "R19") (pin "1") (pinfunction "1_1") (pintype "passive"))
      (node (ref "U1") (pin "17") (pinfunction "PB5(SCK)_17") (pintype "bidirectional"))
      (node (ref "U3") (pin "14") (pinfunction "PB5/D13/SCK_14") (pintype "bidirectional"))
      (node (ref "U3") (pin "37") (pinfunction "SCK_37") (pintype "bidirectional"))
    )
    (net (code "55") (name "PC0") (class "Default")
      (node (ref "PC2") (pin "1") (pinfunction "1_1") (pintype "bidirectional"))
      (node (ref "U1") (pin "23") (pinfunction "PC0(ADC0)_23") (pintype "bidirectional"))
      (node (ref "U3") (pin "19") (pinfunction "PC0/AD0/D14_19") (pintype "bidirectional"))
    )
    (net (code "56") (name "PC1") (class "Default")
      (node (ref "PC2") (pin "2") (pinfunction "2_2") (pintype "bidirectional"))
      (node (ref "U1") (pin "24") (pinfunction "PC1(ADC1)_24") (pintype "bidirectional"))
      (node (ref "U3") (pin "20") (pinfunction "PC1/AD1/D15_20") (pintype "bidirectional"))
    )
    (net (code "57") (name "PC2") (class "Default")
      (node (ref "PC2") (pin "3") (pinfunction "3_3") (pintype "bidirectional"))
      (node (ref "U1") (pin "25") (pinfunction "PC2(ADC2)_25") (pintype "bidirectional"))
      (node (ref "U3") (pin "21") (pinfunction "PC2/AD2/D16_21") (pintype "bidirectional"))
    )
    (net (code "58") (name "PC3") (class "Default")
      (node (ref "PC2") (pin "4") (pinfunction "4_4") (pintype "bidirectional"))
      (node (ref "U1") (pin "26") (pinfunction "PC3(ADC3)_26") (pintype "bidirectional"))
      (node (ref "U3") (pin "22") (pinfunction "PC3/AD3/D17_22") (pintype "bidirectional"))
    )
    (net (code "59") (name "PC4{slash}SDA") (class "Default")
      (node (ref "I2C") (pin "2") (pinfunction "2_2") (pintype "bidirectional"))
      (node (ref "PC2") (pin "5") (pinfunction "5_5") (pintype "bidirectional"))
      (node (ref "PC3") (pin "9") (pinfunction "9_9") (pintype "bidirectional"))
      (node (ref "U1") (pin "27") (pinfunction "PC4(ADC4/SDA)_27") (pintype "bidirectional"))
      (node (ref "U3") (pin "17") (pinfunction "SDA_17") (pintype "bidirectional"))
      (node (ref "U3") (pin "23") (pinfunction "PC4/AD4/D18/SDA_23") (pintype "bidirectional"))
    )
    (net (code "60") (name "PC5{slash}SCL") (class "Default")
      (node (ref "I2C") (pin "1") (pinfunction "1_1") (pintype "bidirectional"))
      (node (ref "PC2") (pin "6") (pinfunction "6_6") (pintype "bidirectional"))
      (node (ref "PC3") (pin "10") (pinfunction "10_10") (pintype "bidirectional"))
      (node (ref "U1") (pin "28") (pinfunction "PC5(ADC5/SCL)_28") (pintype "bidirectional"))
      (node (ref "U3") (pin "18") (pinfunction "SCL_18") (pintype "bidirectional"))
      (node (ref "U3") (pin "24") (pinfunction "PC5/AD5/D19/SCL_24") (pintype "bidirectional"))
    )
    (net (code "61") (name "PD0{slash}RX") (class "Default")
      (node (ref "PC4") (pin "1") (pinfunction "1_1") (pintype "bidirectional"))
      (node (ref "R7") (pin "2") (pinfunction "2_2") (pintype "passive"))
      (node (ref "U1") (pin "30") (pinfunction "PD0(RXD)_30") (pintype "bidirectional"))
      (node (ref "U3") (pin "1") (pinfunction "PD0/D0/RX_1") (pintype "bidirectional"))
      (node (ref "UART") (pin "1") (pinfunction "1_1") (pintype "bidirectional"))
    )
    (net (code "62") (name "PD1{slash}TX") (class "Default")
      (node (ref "PC4") (pin "2") (pinfunction "2_2") (pintype "bidirectional"))
      (node (ref "R15") (pin "2") (pinfunction "2_2") (pintype "passive"))
      (node (ref "U1") (pin "31") (pinfunction "PD1(TXD)_31") (pintype "bidirectional"))
      (node (ref "U3") (pin "2") (pinfunction "PD1/D1/TX_2") (pintype "bidirectional"))
      (node (ref "UART") (pin "2") (pinfunction "2_2") (pintype "bidirectional"))
    )
    (net (code "63") (name "PD2{slash}INT0") (class "Default")
      (node (ref "PC4") (pin "3") (pinfunction "3_3") (pintype "bidirectional"))
      (node (ref "U1") (pin "32") (pinfunction "PD2(INT0)_32") (pintype "bidirectional"))
      (node (ref "U3") (pin "3") (pinfunction "PD2/D2/INT0_3") (pintype "bidirectional"))
    )
    (net (code "64") (name "PD3{slash}INT1") (class "Default")
      (node (ref "PC4") (pin "4") (pinfunction "4_4") (pintype "bidirectional"))
      (node (ref "U1") (pin "1") (pinfunction "PD3(INT1)_1") (pintype "bidirectional"))
      (node (ref "U3") (pin "4") (pinfunction "PD3/D3/INT1/PWM_4") (pintype "bidirectional"))
    )
    (net (code "65") (name "PD4") (class "Default")
      (node (ref "PC4") (pin "5") (pinfunction "5_5") (pintype "bidirectional"))
      (node (ref "U1") (pin "2") (pinfunction "PD4(XCK/T0)_2") (pintype "bidirectional"))
      (node (ref "U3") (pin "5") (pinfunction "PD4/D4_5") (pintype "bidirectional"))
    )
    (net (code "66") (name "PD5") (class "Default")
      (node (ref "PC4") (pin "6") (pinfunction "6_6") (pintype "bidirectional"))
      (node (ref "U1") (pin "9") (pinfunction "PD5(T1)_9") (pintype "bidirectional"))
      (node (ref "U3") (pin "6") (pinfunction "PD5/D5/PWM_6") (pintype "bidirectional"))
    )
    (net (code "67") (name "PD6") (class "Default")
      (node (ref "PC4") (pin "7") (pinfunction "7_7") (pintype "bidirectional"))
      (node (ref "U1") (pin "10") (pinfunction "PD6(AIN0)_10") (pintype "bidirectional"))
      (node (ref "U3") (pin "7") (pinfunction "PD6/D6/PWM_7") (pintype "bidirectional"))
    )
    (net (code "68") (name "PD7") (class "Default")
      (node (ref "PC4") (pin "8") (pinfunction "8_8") (pintype "bidirectional"))
      (node (ref "U1") (pin "11") (pinfunction "PD7(AIN1)_11") (pintype "bidirectional"))
      (node (ref "U3") (pin "8") (pinfunction "PD7/D7_8") (pintype "bidirectional"))
    )
    (net (code "69") (name "RES") (class "Default")
      (node (ref "D2") (pin "+") (pinfunction "+_+") (pintype "passive"))
      (node (ref "ICSP") (pin "3") (pinfunction "3_3") (pintype "bidirectional"))
      (node (ref "R25") (pin "1") (pinfunction "1_1") (pintype "passive"))
      (node (ref "U5") (pin "24") (pinfunction "~{RESET}(PC1/DW)_24") (pintype "bidirectional"))
    )
    (net (code "70") (name "RESET") (class "Default")
      (node (ref "C14") (pin "2") (pinfunction "2_2") (pintype "passive"))
      (node (ref "D3") (pin "+") (pinfunction "+_+") (pintype "passive"))
      (node (ref "PC1") (pin "6") (pinfunction "6_6") (pintype "bidirectional"))
      (node (ref "R5") (pin "2") (pinfunction "2_2") (pintype "passive"))
      (node (ref "RST") (pin "-") (pinfunction "-_-") (pintype "passive"))
      (node (ref "SW1") (pin "1") (pinfunction "1_1") (pintype "bidirectional"))
      (node (ref "U1") (pin "29") (pinfunction "PC6(/RESET)_29") (pintype "bidirectional"))
      (node (ref "U3") (pin "30") (pinfunction "RESET_30") (pintype "bidirectional"))
      (node (ref "U3") (pin "36") (pinfunction "RST_36") (pintype "bidirectional"))
    )
    (net (code "71") (name "SCK") (class "Default")
      (node (ref "ICSP") (pin "2") (pinfunction "2_2") (pintype "bidirectional"))
      (node (ref "U5") (pin "15") (pinfunction "(SCLK/PCINT1)PB1_15") (pintype "bidirectional"))
    )
    (net (code "72") (name "USB5V") (class "Default")
      (node (ref "C10") (pin "2") (pinfunction "2_2") (pintype "passive"))
      (node (ref "C13") (pin "2") (pinfunction "2_2") (pintype "passive"))
      (node (ref "Q16") (pin "3") (pinfunction "D_3") (pintype "passive"))
      (node (ref "U5") (pin "31") (pinfunction "UVCC_31") (pintype "bidirectional"))
      (node (ref "U5V") (pin "T") (pinfunction "T_T") (pintype "bidirectional"))
      (node (ref "USB") (pin "1") (pinfunction "VCC_1") (pintype "bidirectional"))
    )
    (net (code "73") (name "VCC") (class "Default")
      (node (ref "C11") (pin "2") (pinfunction "2_2") (pintype "passive"))
      (node (ref "C23") (pin "2") (pinfunction "2_2") (pintype "passive"))
      (node (ref "C24") (pin "2") (pinfunction "2_2") (pintype "passive"))
      (node (ref "C3") (pin "1") (pinfunction "1_1") (pintype "passive"))
      (node (ref "C41") (pin "2") (pinfunction "2_2") (pintype "passive"))
      (node (ref "C9") (pin "2") (pinfunction "2_2") (pintype "passive"))
      (node (ref "D2") (pin "-") (pinfunction "-_-") (pintype "passive"))
      (node (ref "D3") (pin "-") (pinfunction "-_-") (pintype "passive"))
      (node (ref "I2C") (pin "3") (pinfunction "3_3") (pintype "bidirectional"))
      (node (ref "ICSP") (pin "6") (pinfunction "6_6") (pintype "bidirectional"))
      (node (ref "J3") (pin "1") (pinfunction "1_1") (pintype "bidirectional"))
      (node (ref "Q3") (pin "2") (pinfunction "S_2") (pintype "passive"))
      (node (ref "Q4") (pin "3") (pinfunction "D_3") (pintype "passive"))
      (node (ref "R10") (pin "2") (pinfunction "2_2") (pintype "passive"))
      (node (ref "R25") (pin "2") (pinfunction "2_2") (pintype "passive"))
      (node (ref "R3") (pin "1") (pinfunction "1_1") (pintype "passive"))
      (node (ref "R4") (pin "1") (pinfunction "1_1") (pintype "passive"))
      (node (ref "R5") (pin "1") (pinfunction "1_1") (pintype "passive"))
      (node (ref "R6") (pin "1") (pinfunction "1_1") (pintype "passive"))
      (node (ref "R9") (pin "2") (pinfunction "2_2") (pintype "passive"))
      (node (ref "U1") (pin "18") (pinfunction "AVCC_18") (pintype "bidirectional"))
      (node (ref "U1") (pin "4") (pinfunction "VCC_4") (pintype "bidirectional"))
      (node (ref "U1") (pin "6") (pinfunction "VCC_6") (pintype "bidirectional"))
      (node (ref "U3") (pin "33") (pinfunction "VCC_33") (pintype "bidirectional"))
      (node (ref "U5") (pin "32") (pinfunction "AVCC_32") (pintype "bidirectional"))
      (node (ref "U5") (pin "4") (pinfunction "VCC_4") (pintype "bidirectional"))
      (node (ref "UART") (pin "3") (pinfunction "3_3") (pintype "bidirectional"))
    )
    (net (code "74") (name "XTAL1") (class "Default")
      (node (ref "C6") (pin "2") (pinfunction "2_2") (pintype "passive"))
      (node (ref "U1") (pin "7") (pinfunction "PB6(XTAL1/TOSC1)_7") (pintype "bidirectional"))
      (node (ref "X1") (pin "2") (pinfunction "2_2") (pintype "passive"))
    )
    (net (code "75") (name "XTAL2") (class "Default")
      (node (ref "C8") (pin "2") (pinfunction "2_2") (pintype "passive"))
      (node (ref "U1") (pin "8") (pinfunction "PB7(XTAL2/TOSC2)_8") (pintype "bidirectional"))
      (node (ref "X1") (pin "1") (pinfunction "1_1") (pintype "passive"))
    )
    (net (code "76") (name "XTAL11") (class "Default")
      (node (ref "C12") (pin "2") (pinfunction "2_2") (pintype "passive"))
      (node (ref "U5") (pin "2") (pinfunction "XTAL2(PC0)_2") (pintype "bidirectional"))
      (node (ref "X2") (pin "2") (pinfunction "2_2") (pintype "passive"))
    )
    (net (code "77") (name "XTAL21") (class "Default")
      (node (ref "C27") (pin "2") (pinfunction "2_2") (pintype "passive"))
      (node (ref "U5") (pin "1") (pinfunction "XTAL1_1") (pintype "bidirectional"))
      (node (ref "X2") (pin "1") (pinfunction "1_1") (pintype "passive"))
    )
    (net (code "78") (name "unconnected-(U1-ADC6-Pad19)") (class "Default")
      (node (ref "U1") (pin "19") (pinfunction "ADC6_19") (pintype "bidirectional"))
    )
    (net (code "79") (name "unconnected-(U1-ADC7-Pad22)") (class "Default")
      (node (ref "U1") (pin "22") (pinfunction "ADC7_22") (pintype "bidirectional"))
    )
    (net (code "80") (name "unconnected-(U5-(AIN0{slash}INT1)PD1-Pad7)") (class "Default")
      (node (ref "U5") (pin "7") (pinfunction "(AIN0/INT1)PD1_7") (pintype "bidirectional"))
    )
    (net (code "81") (name "unconnected-(U5-(INT4{slash}ICP1{slash}CLKO)PC7-Pad22)") (class "Default")
      (node (ref "U5") (pin "22") (pinfunction "(INT4/ICP1/CLKO)PC7_22") (pintype "bidirectional"))
    )
    (net (code "82") (name "unconnected-(U5-(OC.1A{slash}PCINT8)PC6-Pad23)") (class "Default")
      (node (ref "U5") (pin "23") (pinfunction "(OC.1A/PCINT8)PC6_23") (pintype "bidirectional"))
    )
    (net (code "83") (name "unconnected-(U5-(OC0B{slash}INT0)PD0-Pad6)") (class "Default")
      (node (ref "U5") (pin "6") (pinfunction "(OC0B/INT0)PD0_6") (pintype "bidirectional"))
    )
    (net (code "84") (name "unconnected-(U5-(PCINT9{slash}OC1B)PC5-Pad25)") (class "Default")
      (node (ref "U5") (pin "25") (pinfunction "(PCINT9/OC1B)PC5_25") (pintype "bidirectional"))
    )
    (net (code "85") (name "unconnected-(U5-(PCINT10)PC4-Pad26)") (class "Default")
      (node (ref "U5") (pin "26") (pinfunction "(PCINT10)PC4_26") (pintype "bidirectional"))
    )
    (net (code "86") (name "unconnected-(U5-(PCINT11{slash}AIN2)PC2-Pad5)") (class "Default")
      (node (ref "U5") (pin "5") (pinfunction "(PCINT11/AIN2)PC2_5") (pintype "bidirectional"))
    )
    (net (code "87") (name "unconnected-(U5-(~{RTS}{slash}AIN5{slash}INT6)PD6-Pad12)") (class "Default")
      (node (ref "U5") (pin "12") (pinfunction "(~{RTS}/AIN5/INT6)PD6_12") (pintype "bidirectional"))
    )
    (net (code "88") (name "unconnected-(U5-(~{SS}{slash}PCINT0)PB0-Pad14)") (class "Default")
      (node (ref "U5") (pin "14") (pinfunction "(~{SS}/PCINT0)PB0_14") (pintype "bidirectional"))
    )
    (net (code "89") (name "unconnected-(USB-ID-Pad4)") (class "Default")
      (node (ref "USB") (pin "4") (pinfunction "ID_4") (pintype "bidirectional"))
    )
  )
)
